# DUAL_CKT.net
KiCad netlist of a schematic drawn in EAGLE
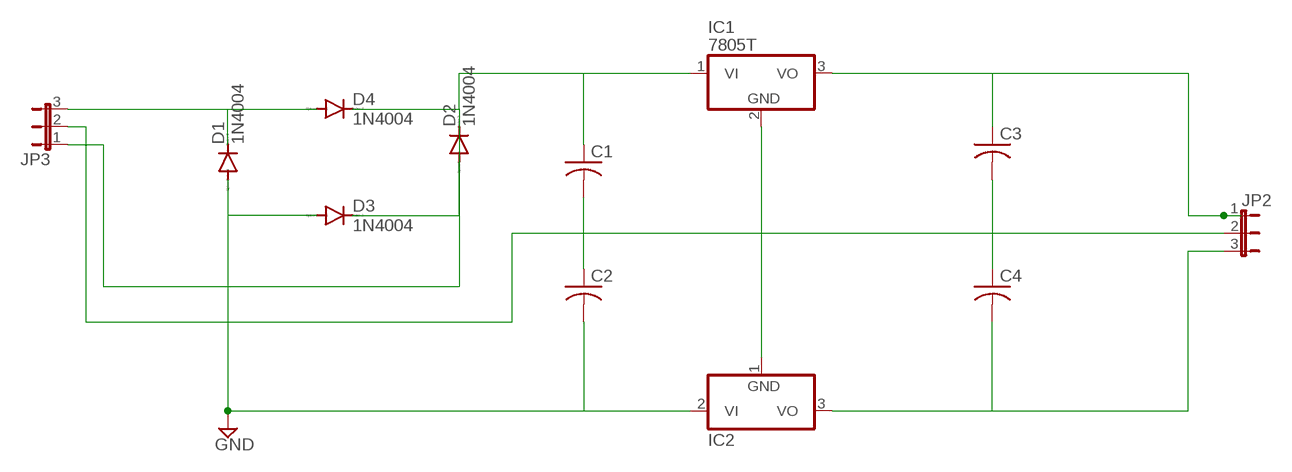
[diagram p0: schematic, sheet 1]

(export (version "E")
  (design (tool "Eeschema 10.0.6"))
  (components
    (comp (ref "C1")
      (value "C-US025-024X044")
      (footprint "eagle-import:C025-024X044")
      (libsource (lib "eagle-import") (part "C-US025-024X044"))
    )
    (comp (ref "C2")
      (value "C-US025-024X044")
      (footprint "eagle-import:C025-024X044")
      (libsource (lib "eagle-import") (part "C-US025-024X044"))
    )
    (comp (ref "C3")
      (value "C-US025-024X044")
      (footprint "eagle-import:C025-024X044")
      (libsource (lib "eagle-import") (part "C-US025-024X044"))
    )
    (comp (ref "C4")
      (value "C-US025-024X044")
      (footprint "eagle-import:C025-024X044")
      (libsource (lib "eagle-import") (part "C-US025-024X044"))
    )
    (comp (ref "D1")
      (value "1N4004")
      (footprint "eagle-import:DO41-10")
      (libsource (lib "eagle-import") (part "1N4004"))
    )
    (comp (ref "D2")
      (value "1N4004")
      (footprint "eagle-import:DO41-10")
      (libsource (lib "eagle-import") (part "1N4004"))
    )
    (comp (ref "D3")
      (value "1N4004")
      (footprint "eagle-import:DO41-10")
      (libsource (lib "eagle-import") (part "1N4004"))
    )
    (comp (ref "D4")
      (value "1N4004")
      (footprint "eagle-import:DO41-10")
      (libsource (lib "eagle-import") (part "1N4004"))
    )
    (comp (ref "IC1")
      (value "7805T")
      (footprint "eagle-import:TO220H")
      (libsource (lib "eagle-import") (part "78T05"))
    )
    (comp (ref "IC2")
      (value "7905T")
      (footprint "eagle-import:TO220H")
      (libsource (lib "eagle-import") (part "79T05"))
    )
    (comp (ref "JP2")
      (value "JP2W")
      (footprint "eagle-import:JP2W")
      (libsource (lib "eagle-import") (part "JP2W"))
    )
    (comp (ref "JP3")
      (value "JP2W")
      (footprint "eagle-import:JP2W")
      (libsource (lib "eagle-import") (part "JP2W"))
    )
  )
  (nets
    (net (code "1") (name "GND") (class "Default")
      (node (ref "C2") (pin "2") (pinfunction "2_2") (pintype "passive"))
      (node (ref "D1") (pin "A") (pinfunction "A_A") (pintype "passive"))
      (node (ref "D3") (pin "A") (pinfunction "A_A") (pintype "passive"))
      (node (ref "IC2") (pin "2") (pinfunction "VI_2") (pintype "input"))
    )
    (net (code "2") (name "Net-(C1-Pad2)") (class "Default")
      (node (ref "C1") (pin "2") (pinfunction "2_2") (pintype "passive"))
      (node (ref "C2") (pin "1") (pinfunction "1_1") (pintype "passive"))
    )
    (net (code "3") (name "Net-(C3-Pad2)") (class "Default")
      (node (ref "C3") (pin "2") (pinfunction "2_2") (pintype "passive"))
      (node (ref "C4") (pin "1") (pinfunction "1_1") (pintype "passive"))
    )
    (net (code "4") (name "Net-(D1-PadC)") (class "Default")
      (node (ref "D1") (pin "C") (pinfunction "C_C") (pintype "passive"))
      (node (ref "D4") (pin "A") (pinfunction "A_A") (pintype "passive"))
      (node (ref "JP3") (pin "3") (pinfunction "3_3") (pintype "passive"))
    )
    (net (code "5") (name "Net-(D2-PadA)") (class "Default")
      (node (ref "D2") (pin "A") (pinfunction "A_A") (pintype "passive"))
      (node (ref "D3") (pin "C") (pinfunction "C_C") (pintype "passive"))
    )
    (net (code "6") (name "Net-(IC1-GND)") (class "Default")
      (node (ref "IC1") (pin "2") (pinfunction "GND_2") (pintype "passive"))
      (node (ref "IC2") (pin "1") (pinfunction "GND_1") (pintype "passive"))
    )
    (net (code "7") (name "Net-(IC1-VI)") (class "Default")
      (node (ref "C1") (pin "1") (pinfunction "1_1") (pintype "passive"))
      (node (ref "D2") (pin "C") (pinfunction "C_C") (pintype "passive"))
      (node (ref "D4") (pin "C") (pinfunction "C_C") (pintype "passive"))
      (node (ref "IC1") (pin "1") (pinfunction "VI_1") (pintype "input"))
      (node (ref "JP3") (pin "1") (pinfunction "1_1") (pintype "passive"))
    )
    (net (code "8") (name "Net-(IC1-VO)") (class "Default")
      (node (ref "C3") (pin "1") (pinfunction "1_1") (pintype "passive"))
      (node (ref "IC1") (pin "3") (pinfunction "VO_3") (pintype "passive"))
      (node (ref "JP2") (pin "1") (pinfunction "1_1") (pintype "passive"))
    )
    (net (code "9") (name "Net-(IC2-VO)") (class "Default")
      (node (ref "C4") (pin "2") (pinfunction "2_2") (pintype "passive"))
      (node (ref "IC2") (pin "3") (pinfunction "VO_3") (pintype "passive"))
      (node (ref "JP2") (pin "3") (pinfunction "3_3") (pintype "passive"))
    )
    (net (code "10") (name "Net-(JP2-Pad2)") (class "Default")
      (node (ref "JP2") (pin "2") (pinfunction "2_2") (pintype "passive"))
      (node (ref "JP3") (pin "2") (pinfunction "2_2") (pintype "passive"))
    )
  )
)
